# CC2530EV.net
KiCad netlist of a schematic drawn in EAGLE
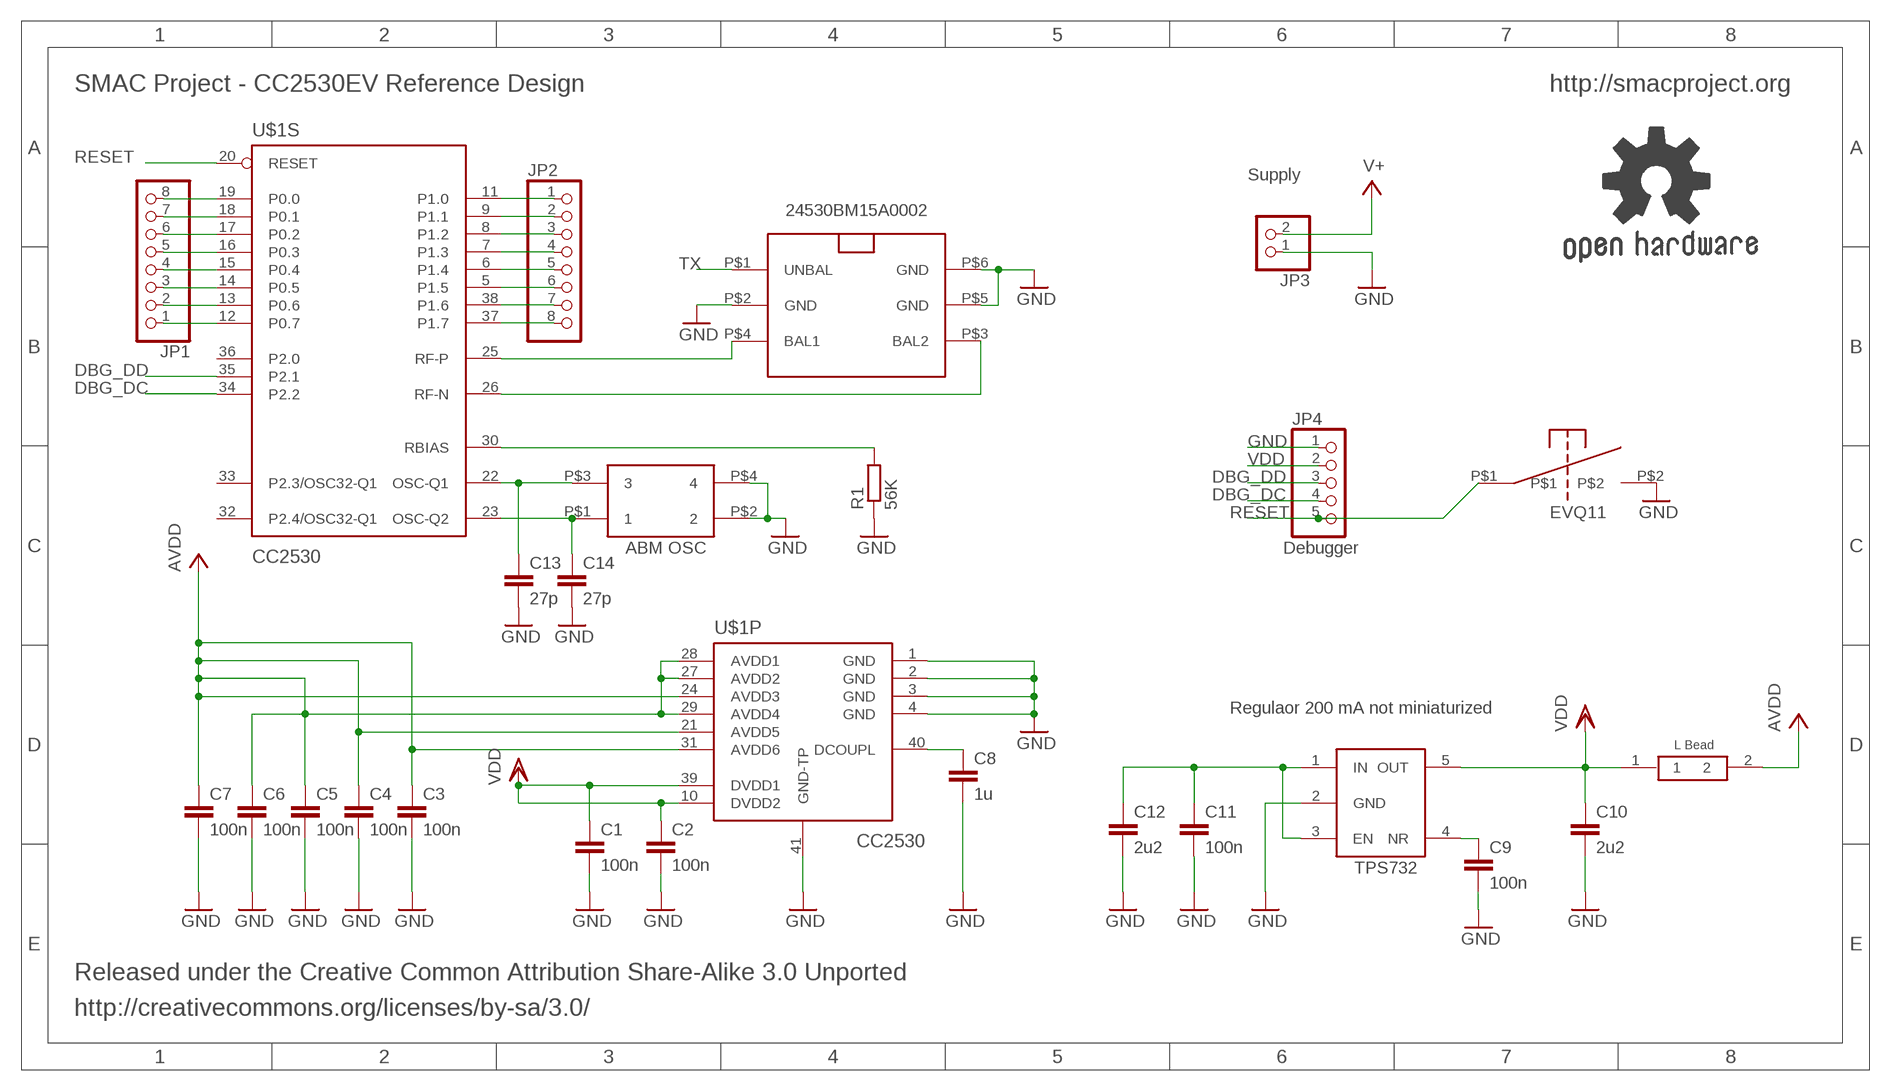
[diagram p0: schematic, sheet 1]

(export (version "E")
  (design (tool "Eeschema 10.0.6"))
  (components
    (comp (ref "C1")
      (value "100n")
      (footprint "eagle-import:C0402")
      (libsource (lib "eagle-import") (part "C-EUC0402"))
    )
    (comp (ref "C2")
      (value "100n")
      (footprint "eagle-import:C0402")
      (libsource (lib "eagle-import") (part "C-EUC0402"))
    )
    (comp (ref "C3")
      (value "100n")
      (footprint "eagle-import:C0402")
      (libsource (lib "eagle-import") (part "C-EUC0402"))
    )
    (comp (ref "C4")
      (value "100n")
      (footprint "eagle-import:C0402")
      (libsource (lib "eagle-import") (part "C-EUC0402"))
    )
    (comp (ref "C5")
      (value "100n")
      (footprint "eagle-import:C0402")
      (libsource (lib "eagle-import") (part "C-EUC0402"))
    )
    (comp (ref "C6")
      (value "100n")
      (footprint "eagle-import:C0402")
      (libsource (lib "eagle-import") (part "C-EUC0402"))
    )
    (comp (ref "C7")
      (value "100n")
      (footprint "eagle-import:C0402")
      (libsource (lib "eagle-import") (part "C-EUC0402"))
    )
    (comp (ref "C8")
      (value "1u")
      (footprint "eagle-import:C0402")
      (libsource (lib "eagle-import") (part "C-EUC0402"))
    )
    (comp (ref "C9")
      (value "100n")
      (footprint "eagle-import:C0402")
      (libsource (lib "eagle-import") (part "C-EUC0402"))
    )
    (comp (ref "C10")
      (value "2u2")
      (footprint "eagle-import:C0402")
      (libsource (lib "eagle-import") (part "C-EUC0402"))
    )
    (comp (ref "C11")
      (value "100n")
      (footprint "eagle-import:C0402")
      (libsource (lib "eagle-import") (part "C-EUC0402"))
    )
    (comp (ref "C12")
      (value "2u2")
      (footprint "eagle-import:C0402")
      (libsource (lib "eagle-import") (part "C-EUC0402"))
    )
    (comp (ref "C13")
      (value "27p")
      (footprint "eagle-import:C0402")
      (libsource (lib "eagle-import") (part "C-EUC0402"))
    )
    (comp (ref "C14")
      (value "27p")
      (footprint "eagle-import:C0402")
      (libsource (lib "eagle-import") (part "C-EUC0402"))
    )
    (comp (ref "GOLD_ORB_SM1")
      (value "OSHWLOGO_GOLD_ORB_SM")
      (footprint "eagle-import:OSHW2")
      (libsource (lib "eagle-import") (part "OSHWLOGO_GOLD_ORB_SM"))
    )
    (comp (ref "JP1")
      (value "PINHD-1X8")
      (footprint "eagle-import:1X08")
      (libsource (lib "eagle-import") (part "PINHD-1X8"))
    )
    (comp (ref "JP2")
      (value "PINHD-1X8")
      (footprint "eagle-import:1X08")
      (libsource (lib "eagle-import") (part "PINHD-1X8"))
    )
    (comp (ref "JP3")
      (value "PINHD-1X2")
      (footprint "eagle-import:1X02")
      (libsource (lib "eagle-import") (part "PINHD-1X2"))
    )
    (comp (ref "JP4")
      (value "PINHD-1X5")
      (footprint "eagle-import:1X05")
      (libsource (lib "eagle-import") (part "PINHD-1X5"))
    )
    (comp (ref "L-BEAD")
      (value "L-BEAD")
      (footprint "eagle-import:L-BEAD")
      (libsource (lib "eagle-import") (part "L-BEAD"))
    )
    (comp (ref "R1")
      (value "56K")
      (footprint "eagle-import:R0402")
      (libsource (lib "eagle-import") (part "R-EU_R0402"))
    )
    (comp (ref "U$1")
      (value "CC2530")
      (footprint "eagle-import:QFN50P600X600X100-41N")
      (libsource (lib "eagle-import") (part "CC2530"))
    )
    (comp (ref "U$2")
      (value "24530BM15A0002")
      (footprint "eagle-import:24530BM15A0002")
      (libsource (lib "eagle-import") (part "24530BM15A0002"))
    )
    (comp (ref "U$3")
      (value "TPS732XX")
      (footprint "eagle-import:SOT23")
      (libsource (lib "eagle-import") (part "TPS732XX"))
    )
    (comp (ref "U$4")
      (value "XTAL32M")
      (footprint "eagle-import:2.5X2X0.5")
      (libsource (lib "eagle-import") (part "XTAL32M"))
    )
    (comp (ref "U$5")
      (value "PUSH_BOT")
      (footprint "eagle-import:EVQ_11_TH")
      (libsource (lib "eagle-import") (part "PUSH_BOT"))
    )
  )
  (nets
    (net (code "1") (name "/DBG_DC") (class "Default")
      (node (ref "JP4") (pin "4") (pinfunction "4_4") (pintype "passive"))
      (node (ref "U$1") (pin "34") (pinfunction "P2.2_34") (pintype "bidirectional"))
    )
    (net (code "2") (name "/DBG_DD") (class "Default")
      (node (ref "JP4") (pin "3") (pinfunction "3_3") (pintype "passive"))
      (node (ref "U$1") (pin "35") (pinfunction "P2.1_35") (pintype "bidirectional"))
    )
    (net (code "3") (name "/RESET") (class "Default")
      (node (ref "JP4") (pin "5") (pinfunction "5_5") (pintype "passive"))
      (node (ref "U$1") (pin "20") (pinfunction "RESET_20") (pintype "input"))
      (node (ref "U$5") (pin "P$1") (pinfunction "P$1_P$1") (pintype "bidirectional"))
    )
    (net (code "4") (name "/TX") (class "Default")
      (node (ref "U$2") (pin "P$1") (pinfunction "UNBAL_P$1") (pintype "bidirectional"))
    )
    (net (code "5") (name "AVDD") (class "Default")
      (node (ref "C3") (pin "1") (pinfunction "1_1") (pintype "passive"))
      (node (ref "C4") (pin "1") (pinfunction "1_1") (pintype "passive"))
      (node (ref "C5") (pin "1") (pinfunction "1_1") (pintype "passive"))
      (node (ref "C6") (pin "1") (pinfunction "1_1") (pintype "passive"))
      (node (ref "C7") (pin "1") (pinfunction "1_1") (pintype "passive"))
      (node (ref "L-BEAD") (pin "2") (pinfunction "2_2") (pintype "bidirectional"))
      (node (ref "U$1") (pin "21") (pinfunction "AVDD5_21") (pintype "power_in"))
      (node (ref "U$1") (pin "24") (pinfunction "AVDD3_24") (pintype "power_in"))
      (node (ref "U$1") (pin "27") (pinfunction "AVDD2_27") (pintype "power_in"))
      (node (ref "U$1") (pin "28") (pinfunction "AVDD1_28") (pintype "power_in"))
      (node (ref "U$1") (pin "29") (pinfunction "AVDD4_29") (pintype "power_in"))
      (node (ref "U$1") (pin "31") (pinfunction "AVDD6_31") (pintype "power_in"))
    )
    (net (code "6") (name "GND") (class "Default")
      (node (ref "C1") (pin "2") (pinfunction "2_2") (pintype "passive"))
      (node (ref "C10") (pin "2") (pinfunction "2_2") (pintype "passive"))
      (node (ref "C11") (pin "2") (pinfunction "2_2") (pintype "passive"))
      (node (ref "C12") (pin "2") (pinfunction "2_2") (pintype "passive"))
      (node (ref "C13") (pin "2") (pinfunction "2_2") (pintype "passive"))
      (node (ref "C14") (pin "2") (pinfunction "2_2") (pintype "passive"))
      (node (ref "C2") (pin "2") (pinfunction "2_2") (pintype "passive"))
      (node (ref "C3") (pin "2") (pinfunction "2_2") (pintype "passive"))
      (node (ref "C4") (pin "2") (pinfunction "2_2") (pintype "passive"))
      (node (ref "C5") (pin "2") (pinfunction "2_2") (pintype "passive"))
      (node (ref "C6") (pin "2") (pinfunction "2_2") (pintype "passive"))
      (node (ref "C7") (pin "2") (pinfunction "2_2") (pintype "passive"))
      (node (ref "C8") (pin "2") (pinfunction "2_2") (pintype "passive"))
      (node (ref "C9") (pin "2") (pinfunction "2_2") (pintype "passive"))
      (node (ref "JP3") (pin "1") (pinfunction "1_1") (pintype "passive"))
      (node (ref "JP4") (pin "1") (pinfunction "1_1") (pintype "passive"))
      (node (ref "R1") (pin "1") (pinfunction "1_1") (pintype "passive"))
      (node (ref "U$1") (pin "1") (pinfunction "GND_1") (pintype "power_in"))
      (node (ref "U$1") (pin "2") (pinfunction "GND_2") (pintype "power_in"))
      (node (ref "U$1") (pin "3") (pinfunction "GND_3") (pintype "power_in"))
      (node (ref "U$1") (pin "4") (pinfunction "GND_4") (pintype "power_in"))
      (node (ref "U$1") (pin "41") (pinfunction "GND-TP_41") (pintype "power_in"))
      (node (ref "U$2") (pin "P$2") (pinfunction "GND_P$2") (pintype "power_in"))
      (node (ref "U$2") (pin "P$5") (pinfunction "GND_P$5") (pintype "power_in"))
      (node (ref "U$2") (pin "P$6") (pinfunction "GND_P$6") (pintype "power_in"))
      (node (ref "U$3") (pin "2") (pinfunction "GND_2") (pintype "bidirectional"))
      (node (ref "U$4") (pin "P$2") (pinfunction "2_P$2") (pintype "bidirectional"))
      (node (ref "U$4") (pin "P$4") (pinfunction "4_P$4") (pintype "bidirectional"))
      (node (ref "U$5") (pin "P$2") (pinfunction "P$2_P$2") (pintype "bidirectional"))
    )
    (net (code "7") (name "Net-(U$1A-DCOUPL)") (class "Default")
      (node (ref "C8") (pin "1") (pinfunction "1_1") (pintype "passive"))
      (node (ref "U$1") (pin "40") (pinfunction "DCOUPL_40") (pintype "power_in"))
    )
    (net (code "8") (name "Net-(U$1B-OSC-Q1)") (class "Default")
      (node (ref "C13") (pin "1") (pinfunction "1_1") (pintype "passive"))
      (node (ref "U$1") (pin "22") (pinfunction "OSC-Q1_22") (pintype "bidirectional"))
      (node (ref "U$4") (pin "P$3") (pinfunction "3_P$3") (pintype "bidirectional"))
    )
    (net (code "9") (name "Net-(U$1B-OSC-Q2)") (class "Default")
      (node (ref "C14") (pin "1") (pinfunction "1_1") (pintype "passive"))
      (node (ref "U$1") (pin "23") (pinfunction "OSC-Q2_23") (pintype "bidirectional"))
      (node (ref "U$4") (pin "P$1") (pinfunction "1_P$1") (pintype "bidirectional"))
    )
    (net (code "10") (name "Net-(U$1B-P0.0)") (class "Default")
      (node (ref "JP1") (pin "8") (pinfunction "8_8") (pintype "passive"))
      (node (ref "U$1") (pin "19") (pinfunction "P0.0_19") (pintype "bidirectional"))
    )
    (net (code "11") (name "Net-(U$1B-P0.1)") (class "Default")
      (node (ref "JP1") (pin "7") (pinfunction "7_7") (pintype "passive"))
      (node (ref "U$1") (pin "18") (pinfunction "P0.1_18") (pintype "bidirectional"))
    )
    (net (code "12") (name "Net-(U$1B-P0.2)") (class "Default")
      (node (ref "JP1") (pin "6") (pinfunction "6_6") (pintype "passive"))
      (node (ref "U$1") (pin "17") (pinfunction "P0.2_17") (pintype "bidirectional"))
    )
    (net (code "13") (name "Net-(U$1B-P0.3)") (class "Default")
      (node (ref "JP1") (pin "5") (pinfunction "5_5") (pintype "passive"))
      (node (ref "U$1") (pin "16") (pinfunction "P0.3_16") (pintype "bidirectional"))
    )
    (net (code "14") (name "Net-(U$1B-P0.4)") (class "Default")
      (node (ref "JP1") (pin "4") (pinfunction "4_4") (pintype "passive"))
      (node (ref "U$1") (pin "15") (pinfunction "P0.4_15") (pintype "bidirectional"))
    )
    (net (code "15") (name "Net-(U$1B-P0.5)") (class "Default")
      (node (ref "JP1") (pin "3") (pinfunction "3_3") (pintype "passive"))
      (node (ref "U$1") (pin "14") (pinfunction "P0.5_14") (pintype "bidirectional"))
    )
    (net (code "16") (name "Net-(U$1B-P0.6)") (class "Default")
      (node (ref "JP1") (pin "2") (pinfunction "2_2") (pintype "passive"))
      (node (ref "U$1") (pin "13") (pinfunction "P0.6_13") (pintype "bidirectional"))
    )
    (net (code "17") (name "Net-(U$1B-P0.7)") (class "Default")
      (node (ref "JP1") (pin "1") (pinfunction "1_1") (pintype "passive"))
      (node (ref "U$1") (pin "12") (pinfunction "P0.7_12") (pintype "bidirectional"))
    )
    (net (code "18") (name "Net-(U$1B-P1.0)") (class "Default")
      (node (ref "JP2") (pin "1") (pinfunction "1_1") (pintype "passive"))
      (node (ref "U$1") (pin "11") (pinfunction "P1.0_11") (pintype "bidirectional"))
    )
    (net (code "19") (name "Net-(U$1B-P1.1)") (class "Default")
      (node (ref "JP2") (pin "2") (pinfunction "2_2") (pintype "passive"))
      (node (ref "U$1") (pin "9") (pinfunction "P1.1_9") (pintype "bidirectional"))
    )
    (net (code "20") (name "Net-(U$1B-P1.2)") (class "Default")
      (node (ref "JP2") (pin "3") (pinfunction "3_3") (pintype "passive"))
      (node (ref "U$1") (pin "8") (pinfunction "P1.2_8") (pintype "bidirectional"))
    )
    (net (code "21") (name "Net-(U$1B-P1.3)") (class "Default")
      (node (ref "JP2") (pin "4") (pinfunction "4_4") (pintype "passive"))
      (node (ref "U$1") (pin "7") (pinfunction "P1.3_7") (pintype "bidirectional"))
    )
    (net (code "22") (name "Net-(U$1B-P1.4)") (class "Default")
      (node (ref "JP2") (pin "5") (pinfunction "5_5") (pintype "passive"))
      (node (ref "U$1") (pin "6") (pinfunction "P1.4_6") (pintype "bidirectional"))
    )
    (net (code "23") (name "Net-(U$1B-P1.5)") (class "Default")
      (node (ref "JP2") (pin "6") (pinfunction "6_6") (pintype "passive"))
      (node (ref "U$1") (pin "5") (pinfunction "P1.5_5") (pintype "bidirectional"))
    )
    (net (code "24") (name "Net-(U$1B-P1.6)") (class "Default")
      (node (ref "JP2") (pin "7") (pinfunction "7_7") (pintype "passive"))
      (node (ref "U$1") (pin "38") (pinfunction "P1.6_38") (pintype "bidirectional"))
    )
    (net (code "25") (name "Net-(U$1B-P1.7)") (class "Default")
      (node (ref "JP2") (pin "8") (pinfunction "8_8") (pintype "passive"))
      (node (ref "U$1") (pin "37") (pinfunction "P1.7_37") (pintype "bidirectional"))
    )
    (net (code "26") (name "Net-(U$1B-RBIAS)") (class "Default")
      (node (ref "R1") (pin "2") (pinfunction "2_2") (pintype "passive"))
      (node (ref "U$1") (pin "30") (pinfunction "RBIAS_30") (pintype "bidirectional"))
    )
    (net (code "27") (name "Net-(U$1B-RF-N)") (class "Default")
      (node (ref "U$1") (pin "26") (pinfunction "RF-N_26") (pintype "bidirectional"))
      (node (ref "U$2") (pin "P$3") (pinfunction "BAL2_P$3") (pintype "bidirectional"))
    )
    (net (code "28") (name "Net-(U$1B-RF-P)") (class "Default")
      (node (ref "U$1") (pin "25") (pinfunction "RF-P_25") (pintype "bidirectional"))
      (node (ref "U$2") (pin "P$4") (pinfunction "BAL1_P$4") (pintype "bidirectional"))
    )
    (net (code "29") (name "Net-(U$3-NR)") (class "Default")
      (node (ref "C9") (pin "1") (pinfunction "1_1") (pintype "passive"))
      (node (ref "U$3") (pin "4") (pinfunction "NR_4") (pintype "bidirectional"))
    )
    (net (code "30") (name "V+") (class "Default")
      (node (ref "C11") (pin "1") (pinfunction "1_1") (pintype "passive"))
      (node (ref "C12") (pin "1") (pinfunction "1_1") (pintype "passive"))
      (node (ref "JP3") (pin "2") (pinfunction "2_2") (pintype "passive"))
      (node (ref "U$3") (pin "1") (pinfunction "IN_1") (pintype "bidirectional"))
      (node (ref "U$3") (pin "3") (pinfunction "EN_3") (pintype "bidirectional"))
    )
    (net (code "31") (name "VDD") (class "Default")
      (node (ref "C1") (pin "1") (pinfunction "1_1") (pintype "passive"))
      (node (ref "C10") (pin "1") (pinfunction "1_1") (pintype "passive"))
      (node (ref "C2") (pin "1") (pinfunction "1_1") (pintype "passive"))
      (node (ref "JP4") (pin "2") (pinfunction "2_2") (pintype "passive"))
      (node (ref "L-BEAD") (pin "1") (pinfunction "1_1") (pintype "bidirectional"))
      (node (ref "U$1") (pin "10") (pinfunction "DVDD2_10") (pintype "power_in"))
      (node (ref "U$1") (pin "39") (pinfunction "DVDD1_39") (pintype "power_in"))
      (node (ref "U$3") (pin "5") (pinfunction "OUT_5") (pintype "bidirectional"))
    )
    (net (code "32") (name "unconnected-(U$1B-P2.0-Pad36)") (class "Default")
      (node (ref "U$1") (pin "36") (pinfunction "P2.0_36") (pintype "bidirectional"))
    )
    (net (code "33") (name "unconnected-(U$1B-P2.3{slash}OSC32-Q1-Pad33)") (class "Default")
      (node (ref "U$1") (pin "33") (pinfunction "P2.3/OSC32-Q1_33") (pintype "bidirectional"))
    )
    (net (code "34") (name "unconnected-(U$1B-P2.4{slash}OSC32-Q1-Pad32)") (class "Default")
      (node (ref "U$1") (pin "32") (pinfunction "P2.4/OSC32-Q1_32") (pintype "bidirectional"))
    )
  )
)
